# key.net
KiCad netlist of a schematic drawn in EAGLE
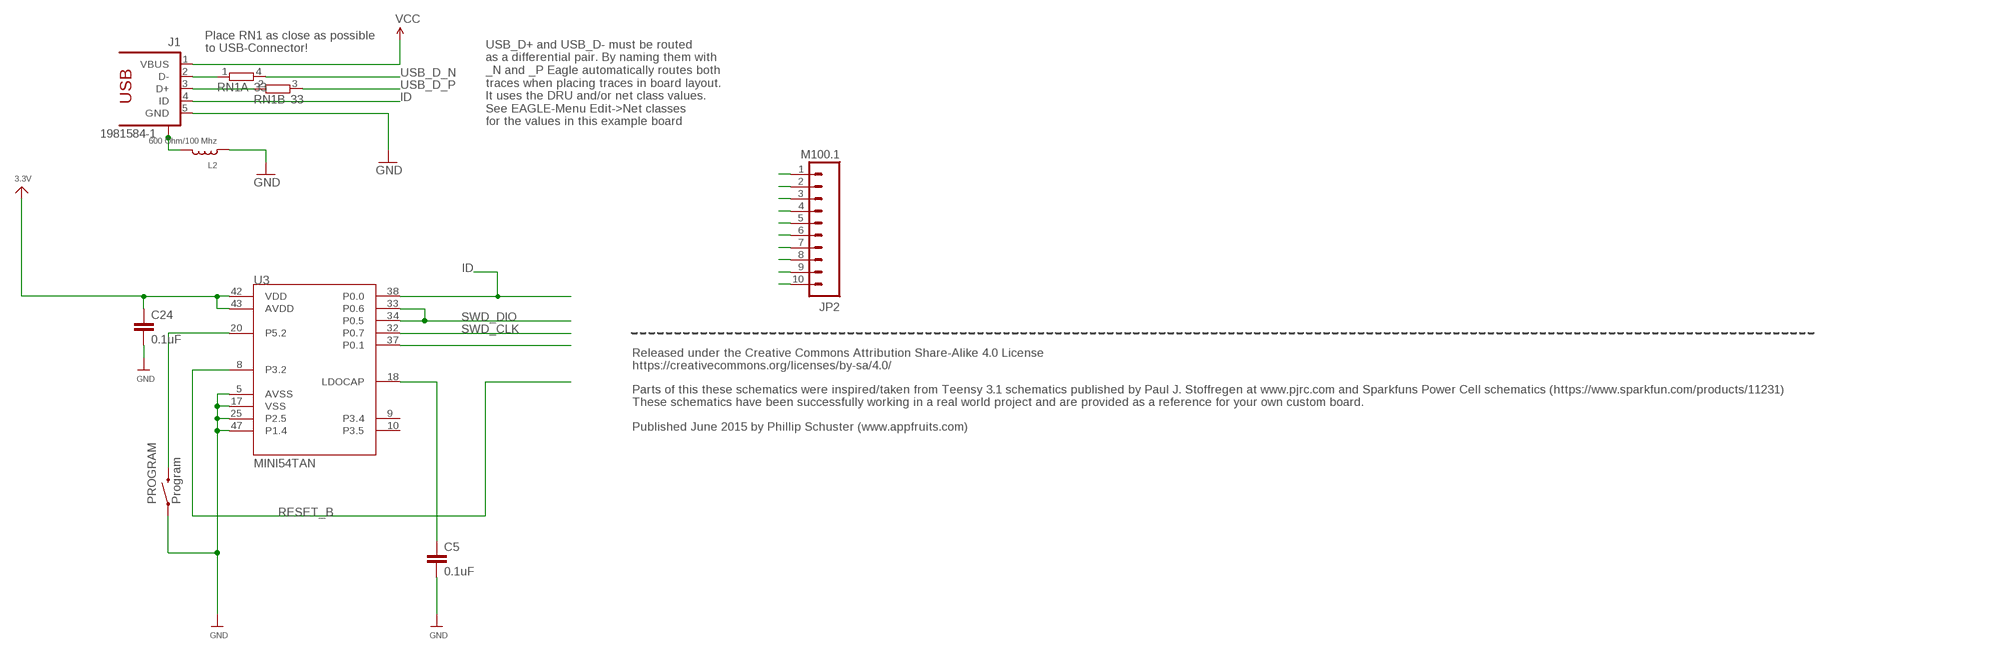
[diagram p0: schematic, sheet 1]

(export (version "E")
  (design (tool "Eeschema 10.0.6"))
  (components
    (comp (ref "C5")
      (value "0.1uF")
      (footprint "eagle-import:0603-CAP")
      (fields (field (name "MF") "Kemet") (field (name "MPN") "C0603C104J3RACTU"))
      (libsource (lib "eagle-import") (part "CAPACITOR-0.1UF"))
    )
    (comp (ref "C24")
      (value "0.1uF")
      (footprint "eagle-import:0603-CAP")
      (fields (field (name "MF") "Kemet") (field (name "MPN") "C0603C104J3RACTU"))
      (libsource (lib "eagle-import") (part "CAPACITOR-0.1UF"))
    )
    (comp (ref "J1")
      (value "1981584-1")
      (footprint "eagle-import:1981584-1")
      (fields (field (name "MF") "Hirose") (field (name "MPN") "ZX62-AB-5PA(11) "))
      (libsource (lib "eagle-import") (part "1981584-1"))
    )
    (comp (ref "JP2")
      (value "M100.1")
      (footprint "eagle-import:1X10")
      (libsource (lib "eagle-import") (part "M100.1"))
    )
    (comp (ref "L2")
      (value "600 Ohm/100 Mhz")
      (footprint "eagle-import:0805")
      (fields (field (name "MF") "Taiyo Yuden") (field (name "MPN") "BK2125HM601-T"))
      (libsource (lib "eagle-import") (part "INDUCTOR-BK2125HM601-T"))
    )
    (comp (ref "PROGRAM")
      (value "Program")
      (footprint "eagle-import:TACTILE-SWITCH-1101NE")
      (fields (field (name "MF") "C&K Components") (field (name "MPN") "RS-282G05A3-SM RT"))
      (libsource (lib "eagle-import") (part "SWITCH-MOMENTARY-2-SMD-1101NE"))
    )
    (comp (ref "RN1")
      (value "33")
      (footprint "eagle-import:EXB34V")
      (fields (field (name "MF") "Panasonic") (field (name "MPN") "EXB-34V330JV"))
      (libsource (lib "eagle-import") (part "2R-NEXB34V"))
    )
    (comp (ref "U3")
      (value "MINI54TAN")
      (footprint "eagle-import:MINI54TAN")
      (libsource (lib "eagle-import") (part "MINI54TAN"))
    )
  )
  (nets
    (net (code "1") (name "/ID") (class "Default")
      (node (ref "J1") (pin "4") (pinfunction "ID_4") (pintype "passive"))
      (node (ref "JP2") (pin "5") (pinfunction "5_5") (pintype "passive"))
      (node (ref "U3") (pin "38") (pinfunction "P0.0_38") (pintype "bidirectional"))
    )
    (net (code "2") (name "/P0.1") (class "Default")
      (node (ref "JP2") (pin "8") (pinfunction "8_8") (pintype "passive"))
      (node (ref "U3") (pin "37") (pinfunction "P0.1_37") (pintype "bidirectional"))
    )
    (net (code "3") (name "/RESET_B") (class "Default")
      (node (ref "JP2") (pin "9") (pinfunction "9_9") (pintype "passive"))
      (node (ref "U3") (pin "8") (pinfunction "P3.2_8") (pintype "bidirectional"))
    )
    (net (code "4") (name "/SWD_CLK") (class "Default")
      (node (ref "JP2") (pin "7") (pinfunction "7_7") (pintype "passive"))
      (node (ref "U3") (pin "32") (pinfunction "P0.7_32") (pintype "bidirectional"))
    )
    (net (code "5") (name "/SWD_DIO") (class "Default")
      (node (ref "JP2") (pin "6") (pinfunction "6_6") (pintype "passive"))
      (node (ref "U3") (pin "33") (pinfunction "P0.6_33") (pintype "bidirectional"))
      (node (ref "U3") (pin "34") (pinfunction "P0.5_34") (pintype "bidirectional"))
    )
    (net (code "6") (name "/USB_D_N") (class "Default")
      (node (ref "JP2") (pin "3") (pinfunction "3_3") (pintype "passive"))
      (node (ref "RN1") (pin "4") (pinfunction "2_4") (pintype "passive"))
    )
    (net (code "7") (name "/USB_D_P") (class "Default")
      (node (ref "JP2") (pin "4") (pinfunction "4_4") (pintype "passive"))
      (node (ref "RN1") (pin "3") (pinfunction "2_3") (pintype "passive"))
    )
    (net (code "8") (name "3.3V") (class "Default")
      (node (ref "C24") (pin "1") (pinfunction "1_1") (pintype "passive"))
      (node (ref "JP2") (pin "10") (pinfunction "10_10") (pintype "passive"))
      (node (ref "U3") (pin "42") (pinfunction "VDD_42") (pintype "bidirectional"))
      (node (ref "U3") (pin "43") (pinfunction "AVDD_43") (pintype "bidirectional"))
    )
    (net (code "9") (name "GND") (class "Default")
      (node (ref "C24") (pin "2") (pinfunction "2_2") (pintype "passive"))
      (node (ref "C5") (pin "2") (pinfunction "2_2") (pintype "passive"))
      (node (ref "J1") (pin "5") (pinfunction "GND_5") (pintype "passive"))
      (node (ref "JP2") (pin "1") (pinfunction "1_1") (pintype "passive"))
      (node (ref "L2") (pin "1") (pinfunction "1_1") (pintype "passive"))
      (node (ref "PROGRAM") (pin "P$1") (pinfunction "1_P$1") (pintype "passive"))
      (node (ref "U3") (pin "17") (pinfunction "VSS_17") (pintype "bidirectional"))
      (node (ref "U3") (pin "25") (pinfunction "P2.5_25") (pintype "bidirectional"))
      (node (ref "U3") (pin "47") (pinfunction "P1.4_47") (pintype "bidirectional"))
      (node (ref "U3") (pin "5") (pinfunction "AVSS_5") (pintype "bidirectional"))
    )
    (net (code "10") (name "Net-(J1-D+)") (class "Default")
      (node (ref "J1") (pin "3") (pinfunction "D+_3") (pintype "passive"))
      (node (ref "RN1") (pin "2") (pinfunction "1_2") (pintype "passive"))
    )
    (net (code "11") (name "Net-(J1-D-)") (class "Default")
      (node (ref "J1") (pin "2") (pinfunction "D-_2") (pintype "passive"))
      (node (ref "RN1") (pin "1") (pinfunction "1_1") (pintype "passive"))
    )
    (net (code "12") (name "Net-(J1-PadS1)") (class "Default")
      (node (ref "J1") (pin "S1") (pinfunction "S1_S1") (pintype "passive"))
      (node (ref "J1") (pin "S2") (pinfunction "S2_S2") (pintype "passive"))
      (node (ref "J1") (pin "S3") (pinfunction "S3_S3") (pintype "passive"))
      (node (ref "J1") (pin "S4") (pinfunction "S4_S4") (pintype "passive"))
      (node (ref "L2") (pin "2") (pinfunction "2_2") (pintype "passive"))
    )
    (net (code "13") (name "Net-(PROGRAM-2)") (class "Default")
      (node (ref "PROGRAM") (pin "P$2") (pinfunction "2_P$2") (pintype "passive"))
      (node (ref "U3") (pin "20") (pinfunction "P5.2_20") (pintype "bidirectional"))
    )
    (net (code "14") (name "Net-(U3-LDOCAP)") (class "Default")
      (node (ref "C5") (pin "1") (pinfunction "1_1") (pintype "passive"))
      (node (ref "U3") (pin "18") (pinfunction "LDOCAP_18") (pintype "bidirectional"))
    )
    (net (code "15") (name "VCC") (class "Default")
      (node (ref "J1") (pin "1") (pinfunction "VBUS_1") (pintype "passive"))
      (node (ref "JP2") (pin "2") (pinfunction "2_2") (pintype "passive"))
    )
    (net (code "16") (name "unconnected-(U3-P3.4-Pad9)") (class "Default")
      (node (ref "U3") (pin "9") (pinfunction "P3.4_9") (pintype "bidirectional"))
    )
    (net (code "17") (name "unconnected-(U3-P3.5-Pad10)") (class "Default")
      (node (ref "U3") (pin "10") (pinfunction "P3.5_10") (pintype "bidirectional"))
    )
  )
)
